# Sheet1.net
KiCad netlist of a schematic drawn in Altium Designer
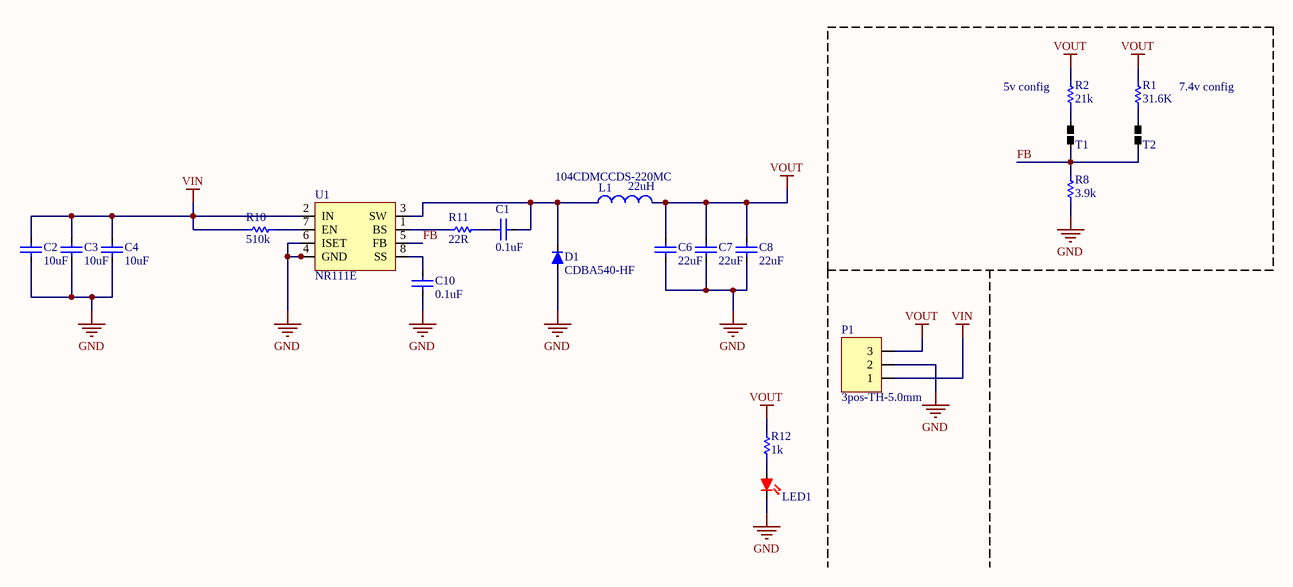
[diagram p0: Sheet1.SchDoc]

(export (version "E")
  (design (tool "Eeschema 10.0.6"))
  (components
    (comp (ref "C1")
      (value "0.1uF")
      (footprint "CAPACITOR-0603")
      (description "Capacitor-0603-0.1uF-50V-X7R")
      (libsource (lib "Capacitors") (part "Capacitor-0603-0.1uF-50V-X7R"))
    )
    (comp (ref "C2")
      (value "10uF")
      (footprint "CAPACITOR-0805")
      (description "Capacitor-0805-10uF-35V-X5R")
      (libsource (lib "Capacitors") (part "Capacitor-0805-10uF-35V-X5R"))
    )
    (comp (ref "C3")
      (value "10uF")
      (footprint "CAPACITOR-0805")
      (description "Capacitor-0805-10uF-35V-X5R")
      (libsource (lib "Capacitors") (part "Capacitor-0805-10uF-35V-X5R"))
    )
    (comp (ref "C4")
      (value "10uF")
      (footprint "CAPACITOR-0805")
      (description "Capacitor-0805-10uF-35V-X5R")
      (libsource (lib "Capacitors") (part "Capacitor-0805-10uF-35V-X5R"))
    )
    (comp (ref "C6")
      (value "22uF")
      (footprint "CAPACITOR-0805")
      (description "Capacitor-0805-22uF-16V-X5R")
      (libsource (lib "Capacitors") (part "Capacitor-0805-22uF-16V-X5R"))
    )
    (comp (ref "C7")
      (value "22uF")
      (footprint "CAPACITOR-0805")
      (description "Capacitor-0805-22uF-16V-X5R")
      (libsource (lib "Capacitors") (part "Capacitor-0805-22uF-16V-X5R"))
    )
    (comp (ref "C8")
      (value "22uF")
      (footprint "CAPACITOR-0805")
      (description "Capacitor-0805-22uF-16V-X5R")
      (libsource (lib "Capacitors") (part "Capacitor-0805-22uF-16V-X5R"))
    )
    (comp (ref "C10")
      (value "0.1uF")
      (footprint "CAPACITOR-0603")
      (description "Capacitor-0603-0.1uF-50V-X7R")
      (libsource (lib "Capacitors") (part "Capacitor-0603-0.1uF-50V-X7R"))
    )
    (comp (ref "D1")
      (value "CDBA540-HF")
      (footprint "SMA/DO-214AC")
      (description "DIODE SCHOTTKY 40V 5A SMA")
      (libsource (lib "diodes") (part "CDBA540-HF"))
    )
    (comp (ref "L1")
      (value "104CDMCCDS-220MC")
      (footprint "Inductor_22UH 5A")
      (description "FIXED IND 22UH 5A 66 MOHM SMD")
      (fields (field (name "ALTIUM_VALUE") "22uH"))
      (libsource (lib "Inductors") (part "104CDMCCDS-220MC"))
    )
    (comp (ref "LED1")
      (value "B1911USD-20D000114U1930")
      (footprint "LED-0603-2PIN")
      (description "LED RED CLEAR 1608 SMD")
      (libsource (lib "LEDs") (part "B1911USD-20D000114U1930"))
    )
    (comp (ref "P1")
      (value "3pos-TH-5.0mm")
      (footprint "Side Connector 3pins")
      (description "3pos-TH-5.0mm Screw Terminal")
      (libsource (lib "ScrewTerminal") (part "3pos-TH-5.0mm"))
    )
    (comp (ref "R1")
      (value "31.6K")
      (footprint "Resistor-0603")
      (description "Resistor")
      (fields (field (name "Comment") "SMT resistor"))
      (libsource (lib "Resistors") (part "Resistor0603-21k"))
    )
    (comp (ref "R2")
      (value "21k")
      (footprint "Resistor-0603")
      (description "Resistor")
      (fields (field (name "Comment") "SMT resistor"))
      (libsource (lib "Resistors") (part "Resistor0603-21k"))
    )
    (comp (ref "R8")
      (value "3.9k")
      (footprint "Resistor-0603")
      (description "Resistor")
      (fields (field (name "Comment") "SMT resistor"))
      (libsource (lib "Resistors") (part "Resistor0603-3.9k"))
    )
    (comp (ref "R10")
      (value "510k")
      (footprint "Resistor-0603")
      (description "Resistor")
      (fields (field (name "Comment") "SMT resistor"))
      (libsource (lib "Resistors") (part "Resistor0603-510k"))
    )
    (comp (ref "R11")
      (value "22R")
      (footprint "Resistor-0603")
      (description "Resistor")
      (fields (field (name "Comment") "SMT resistor"))
      (libsource (lib "Resistors") (part "Resistor0603-22R"))
    )
    (comp (ref "R12")
      (value "1k")
      (footprint "Resistor-0603")
      (description "Resistor")
      (fields (field (name "Comment") "SMT resistor"))
      (libsource (lib "Resistors") (part "Resistor0603-1k"))
    )
    (comp (ref "T1")
      (value "NetTie_0402")
      (footprint "NetTie-0402")
      (libsource (lib "machine2024_SCH") (part "NetTie_0402"))
    )
    (comp (ref "T2")
      (value "NetTie_0402")
      (footprint "NetTie-0402")
      (libsource (lib "machine2024_SCH") (part "NetTie_0402"))
    )
    (comp (ref "U1")
      (value "NR111E")
      (footprint "SOIC-8-EXPOSED-PAD")
      (description "IC REG BUCK ADJUSTABLE 4A 8SOIC")
      (libsource (lib "PMIC-VoltageRegulators-DCDCSwitchingRegulators") (part "NR111E"))
    )
  )
  (nets
    (net (code "1") (name "/FB") (class "Default")
      (node (ref "R8") (pin "2") (pinfunction "2_2") (pintype "passive"))
      (node (ref "T1") (pin "2") (pinfunction "2_2") (pintype "passive"))
      (node (ref "T2") (pin "2") (pinfunction "2_2") (pintype "passive"))
      (node (ref "U1") (pin "5") (pinfunction "FB_5") (pintype "passive"))
    )
    (net (code "2") (name "GND") (class "Default")
      (node (ref "C10") (pin "2") (pinfunction "2_2") (pintype "passive"))
      (node (ref "C2") (pin "1") (pinfunction "1_1") (pintype "passive"))
      (node (ref "C3") (pin "1") (pinfunction "1_1") (pintype "passive"))
      (node (ref "C4") (pin "1") (pinfunction "1_1") (pintype "passive"))
      (node (ref "C6") (pin "1") (pinfunction "1_1") (pintype "passive"))
      (node (ref "C7") (pin "1") (pinfunction "1_1") (pintype "passive"))
      (node (ref "C8") (pin "1") (pinfunction "1_1") (pintype "passive"))
      (node (ref "D1") (pin "1") (pinfunction "A_1") (pintype "passive"))
      (node (ref "LED1") (pin "1") (pinfunction "K_1") (pintype "passive"))
      (node (ref "P1") (pin "2") (pinfunction "2_2") (pintype "passive"))
      (node (ref "R8") (pin "1") (pinfunction "1_1") (pintype "passive"))
      (node (ref "U1") (pin "4") (pinfunction "GND_4") (pintype "passive"))
      (node (ref "U1") (pin "6") (pinfunction "ISET_6") (pintype "passive"))
      (node (ref "U1") (pin "9") (pinfunction "GND_9") (pintype "passive"))
    )
    (net (code "3") (name "Net-(C1-Pad1)") (class "Default")
      (node (ref "C1") (pin "1") (pinfunction "1_1") (pintype "passive"))
      (node (ref "R11") (pin "2") (pinfunction "2_2") (pintype "passive"))
    )
    (net (code "4") (name "Net-(D1-K)") (class "Default")
      (node (ref "C1") (pin "2") (pinfunction "2_2") (pintype "passive"))
      (node (ref "D1") (pin "2") (pinfunction "K_2") (pintype "passive"))
      (node (ref "L1") (pin "1") (pinfunction "1_1") (pintype "passive"))
      (node (ref "U1") (pin "3") (pinfunction "SW_3") (pintype "passive"))
    )
    (net (code "5") (name "Net-(LED1-R)") (class "Default")
      (node (ref "LED1") (pin "2") (pinfunction "R_2") (pintype "passive"))
      (node (ref "R12") (pin "1") (pinfunction "1_1") (pintype "passive"))
    )
    (net (code "6") (name "Net-(R1-Pad1)") (class "Default")
      (node (ref "R1") (pin "1") (pinfunction "1_1") (pintype "passive"))
      (node (ref "T2") (pin "1") (pinfunction "1_1") (pintype "passive"))
    )
    (net (code "7") (name "Net-(R2-Pad1)") (class "Default")
      (node (ref "R2") (pin "1") (pinfunction "1_1") (pintype "passive"))
      (node (ref "T1") (pin "1") (pinfunction "1_1") (pintype "passive"))
    )
    (net (code "8") (name "Net-(U1-BS)") (class "Default")
      (node (ref "R11") (pin "1") (pinfunction "1_1") (pintype "passive"))
      (node (ref "U1") (pin "1") (pinfunction "BS_1") (pintype "passive"))
    )
    (net (code "9") (name "Net-(U1-EN)") (class "Default")
      (node (ref "R10") (pin "2") (pinfunction "2_2") (pintype "passive"))
      (node (ref "U1") (pin "7") (pinfunction "EN_7") (pintype "passive"))
    )
    (net (code "10") (name "Net-(U1-SS)") (class "Default")
      (node (ref "C10") (pin "1") (pinfunction "1_1") (pintype "passive"))
      (node (ref "U1") (pin "8") (pinfunction "SS_8") (pintype "passive"))
    )
    (net (code "11") (name "VIN") (class "Default")
      (node (ref "C2") (pin "2") (pinfunction "2_2") (pintype "passive"))
      (node (ref "C3") (pin "2") (pinfunction "2_2") (pintype "passive"))
      (node (ref "C4") (pin "2") (pinfunction "2_2") (pintype "passive"))
      (node (ref "P1") (pin "1") (pinfunction "1_1") (pintype "passive"))
      (node (ref "R10") (pin "1") (pinfunction "1_1") (pintype "passive"))
      (node (ref "U1") (pin "2") (pinfunction "IN_2") (pintype "passive"))
    )
    (net (code "12") (name "VOUT") (class "Default")
      (node (ref "C6") (pin "2") (pinfunction "2_2") (pintype "passive"))
      (node (ref "C7") (pin "2") (pinfunction "2_2") (pintype "passive"))
      (node (ref "C8") (pin "2") (pinfunction "2_2") (pintype "passive"))
      (node (ref "L1") (pin "2") (pinfunction "2_2") (pintype "passive"))
      (node (ref "P1") (pin "3") (pinfunction "3_3") (pintype "passive"))
      (node (ref "R1") (pin "2") (pinfunction "2_2") (pintype "passive"))
      (node (ref "R12") (pin "2") (pinfunction "2_2") (pintype "passive"))
      (node (ref "R2") (pin "2") (pinfunction "2_2") (pintype "passive"))
    )
  )
)
